# SCH__TX510__2025-04-04.net
KiCad netlist of a schematic drawn in Altium Designer
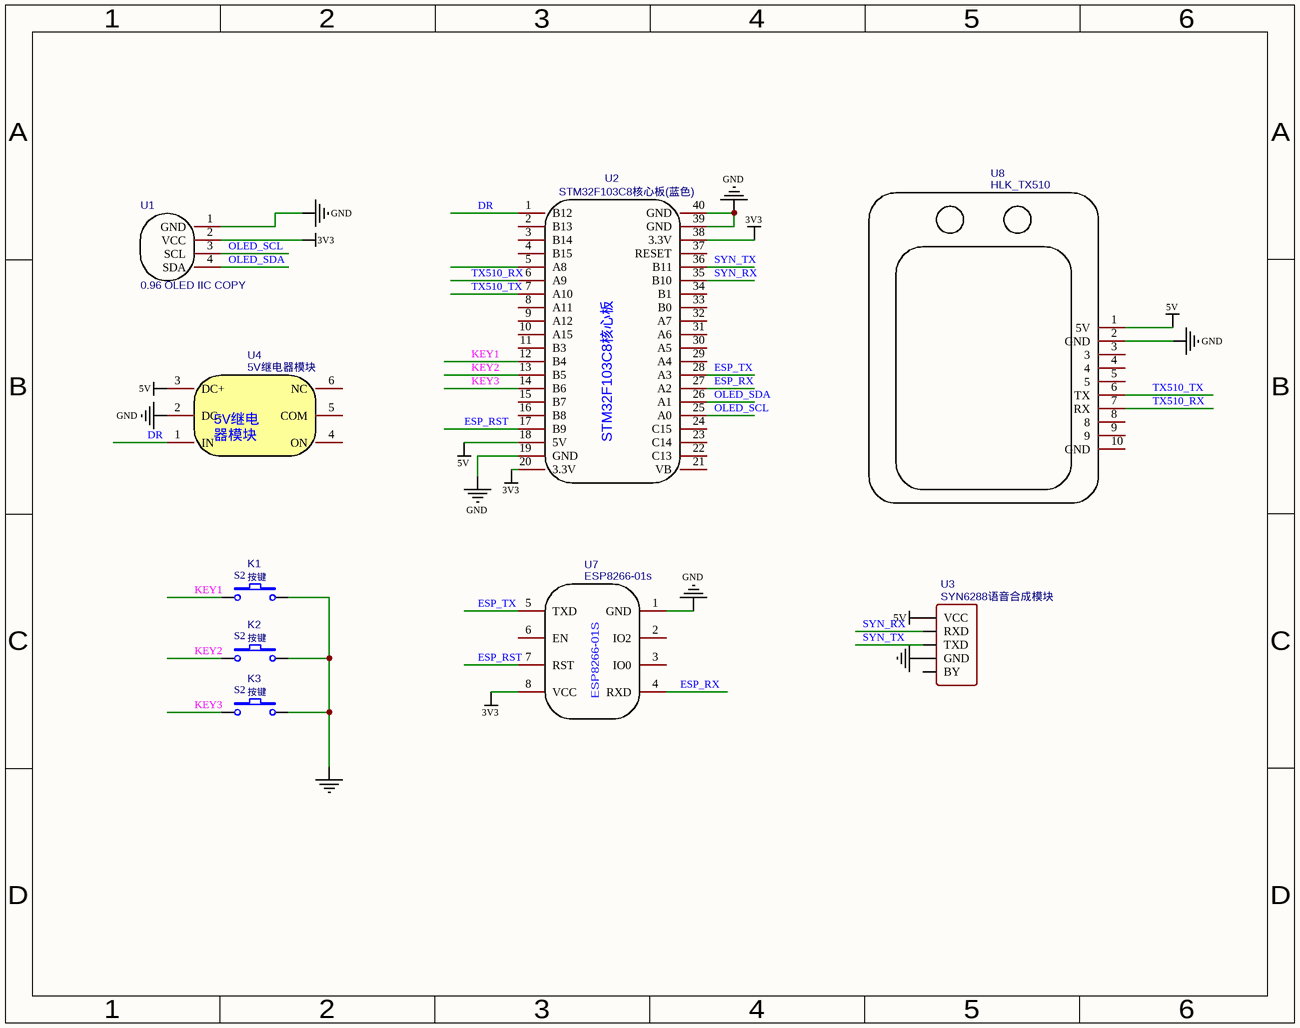
[diagram p0: SCH_人脸识别TX510和考勤_2025-04-04.schdoc]

(export (version "E")
  (design (tool "Eeschema 10.0.6"))
  (components
    (comp (ref "K1")
      (value "按键")
      (footprint "KEY-TH_4P复位按键")
      (fields (field (name "CONTRIBUTOR") "tongtongll"))
      (libsource (lib "altium-import") (part "root_1_按键_"))
    )
    (comp (ref "K2")
      (value "按键")
      (footprint "KEY-TH_4P复位按键")
      (fields (field (name "CONTRIBUTOR") "tongtongll"))
      (libsource (lib "altium-import") (part "root_1_按键_"))
    )
    (comp (ref "K3")
      (value "按键")
      (footprint "KEY-TH_4P复位按键")
      (fields (field (name "CONTRIBUTOR") "tongtongll"))
      (libsource (lib "altium-import") (part "root_1_按键_"))
    )
    (comp (ref "U1")
      (value "0.96 OLED IIC COPY")
      (footprint "OLED-TH_OLED0.96-IIC")
      (fields (field (name "CONTRIBUTOR") "0errors0warning"))
      (libsource (lib "altium-import") (part "root_0_0.96 OLED IIC COPY_"))
    )
    (comp (ref "U2")
      (value "STM32F103C8核心板(蓝色)")
      (footprint "STM32F103C8T6核心板")
      (fields (field (name "CONTRIBUTOR") "JINZH"))
      (libsource (lib "altium-import") (part "root_0_STM32F103C8核心板(蓝色)_"))
    )
    (comp (ref "U3")
      (value "SYN6288语音合成模块")
      (footprint "SYN6288语音合成模块")
      (fields (field (name "CONTRIBUTOR") "qq757683348"))
      (libsource (lib "altium-import") (part "root_0_SYN6288语音合成模块_"))
    )
    (comp (ref "U4")
      (value "5V继电器模块")
      (footprint "5V继电器模块")
      (fields (field (name "CONTRIBUTOR") "zxt_esp8266"))
      (libsource (lib "altium-import") (part "root_2_5V继电器模块_"))
    )
    (comp (ref "U7")
      (value "ESP8266-01s")
      (footprint "ESP8266-01S")
      (fields (field (name "CONTRIBUTOR") "weidu"))
      (libsource (lib "altium-import") (part "root_3_ESP8266-01s_"))
    )
    (comp (ref "U8")
      (value "HLK_TX510")
      (footprint "TX510")
      (fields (field (name "CONTRIBUTOR") "flyinglab"))
      (libsource (lib "altium-import") (part "root_0_HLK_TX510_"))
    )
  )
  (nets
    (net (code "1") (name "/DR") (class "Default")
      (node (ref "U2") (pin "1") (pinfunction "B12_1") (pintype "passive"))
      (node (ref "U4") (pin "1") (pinfunction "IN_1") (pintype "passive"))
    )
    (net (code "2") (name "/ESP_RST") (class "Default")
      (node (ref "U2") (pin "17") (pinfunction "B9_17") (pintype "passive"))
      (node (ref "U7") (pin "7") (pinfunction "RST_7") (pintype "passive"))
    )
    (net (code "3") (name "/ESP_RX") (class "Default")
      (node (ref "U2") (pin "27") (pinfunction "A2_27") (pintype "passive"))
      (node (ref "U7") (pin "4") (pinfunction "RXD_4") (pintype "passive"))
    )
    (net (code "4") (name "/ESP_TX") (class "Default")
      (node (ref "U2") (pin "28") (pinfunction "A3_28") (pintype "passive"))
      (node (ref "U7") (pin "5") (pinfunction "TXD_5") (pintype "passive"))
    )
    (net (code "5") (name "/KEY1") (class "Default")
      (node (ref "K1") (pin "1") (pinfunction "1_1") (pintype "passive"))
      (node (ref "U2") (pin "12") (pinfunction "B4_12") (pintype "passive"))
    )
    (net (code "6") (name "/KEY2") (class "Default")
      (node (ref "K2") (pin "1") (pinfunction "1_1") (pintype "passive"))
      (node (ref "U2") (pin "13") (pinfunction "B5_13") (pintype "passive"))
    )
    (net (code "7") (name "/KEY3") (class "Default")
      (node (ref "K3") (pin "1") (pinfunction "1_1") (pintype "passive"))
      (node (ref "U2") (pin "14") (pinfunction "B6_14") (pintype "passive"))
    )
    (net (code "8") (name "/OLED_SCL") (class "Default")
      (node (ref "U1") (pin "3") (pinfunction "SCL_3") (pintype "passive"))
      (node (ref "U2") (pin "25") (pinfunction "A0_25") (pintype "passive"))
    )
    (net (code "9") (name "/OLED_SDA") (class "Default")
      (node (ref "U1") (pin "4") (pinfunction "SDA_4") (pintype "passive"))
      (node (ref "U2") (pin "26") (pinfunction "A1_26") (pintype "passive"))
    )
    (net (code "10") (name "/SYN_RX") (class "Default")
      (node (ref "U2") (pin "35") (pinfunction "B10_35") (pintype "passive"))
      (node (ref "U3") (pin "2") (pinfunction "RXD_2") (pintype "passive"))
    )
    (net (code "11") (name "/SYN_TX") (class "Default")
      (node (ref "U2") (pin "36") (pinfunction "B11_36") (pintype "passive"))
      (node (ref "U3") (pin "3") (pinfunction "TXD_3") (pintype "passive"))
    )
    (net (code "12") (name "/TX510_RX") (class "Default")
      (node (ref "U2") (pin "6") (pinfunction "A9_6") (pintype "passive"))
      (node (ref "U8") (pin "7") (pinfunction "RX_7") (pintype "passive"))
    )
    (net (code "13") (name "/TX510_TX") (class "Default")
      (node (ref "U2") (pin "7") (pinfunction "A10_7") (pintype "passive"))
      (node (ref "U8") (pin "6") (pinfunction "TX_6") (pintype "passive"))
    )
    (net (code "14") (name "3V3") (class "Default")
      (node (ref "U1") (pin "2") (pinfunction "VCC_2") (pintype "passive"))
      (node (ref "U2") (pin "20") (pinfunction "3.3V_20") (pintype "passive"))
      (node (ref "U2") (pin "38") (pinfunction "3.3V_38") (pintype "passive"))
      (node (ref "U7") (pin "8") (pinfunction "VCC_8") (pintype "passive"))
    )
    (net (code "15") (name "5V") (class "Default")
      (node (ref "U2") (pin "18") (pinfunction "5V_18") (pintype "passive"))
      (node (ref "U3") (pin "1") (pinfunction "VCC_1") (pintype "passive"))
      (node (ref "U4") (pin "3") (pinfunction "DC+_3") (pintype "passive"))
      (node (ref "U8") (pin "1") (pinfunction "5V_1") (pintype "passive"))
    )
    (net (code "16") (name "GND") (class "Default")
      (node (ref "K1") (pin "3") (pinfunction "3_3") (pintype "passive"))
      (node (ref "K2") (pin "3") (pinfunction "3_3") (pintype "passive"))
      (node (ref "K3") (pin "3") (pinfunction "3_3") (pintype "passive"))
      (node (ref "U1") (pin "1") (pinfunction "GND_1") (pintype "passive"))
      (node (ref "U2") (pin "19") (pinfunction "GND_19") (pintype "passive"))
      (node (ref "U2") (pin "39") (pinfunction "GND_39") (pintype "passive"))
      (node (ref "U2") (pin "40") (pinfunction "GND_40") (pintype "passive"))
      (node (ref "U3") (pin "4") (pinfunction "GND_4") (pintype "passive"))
      (node (ref "U4") (pin "2") (pinfunction "DC-_2") (pintype "passive"))
      (node (ref "U7") (pin "1") (pinfunction "GND_1") (pintype "passive"))
      (node (ref "U8") (pin "2") (pinfunction "GND_2") (pintype "passive"))
    )
    (net (code "17") (name "unconnected-(U2-A4-Pad29)") (class "Default")
      (node (ref "U2") (pin "29") (pinfunction "A4_29") (pintype "passive"))
    )
    (net (code "18") (name "unconnected-(U2-A5-Pad30)") (class "Default")
      (node (ref "U2") (pin "30") (pinfunction "A5_30") (pintype "passive"))
    )
    (net (code "19") (name "unconnected-(U2-A6-Pad31)") (class "Default")
      (node (ref "U2") (pin "31") (pinfunction "A6_31") (pintype "passive"))
    )
    (net (code "20") (name "unconnected-(U2-A7-Pad32)") (class "Default")
      (node (ref "U2") (pin "32") (pinfunction "A7_32") (pintype "passive"))
    )
    (net (code "21") (name "unconnected-(U2-A8-Pad5)") (class "Default")
      (node (ref "U2") (pin "5") (pinfunction "A8_5") (pintype "passive"))
    )
    (net (code "22") (name "unconnected-(U2-A11-Pad8)") (class "Default")
      (node (ref "U2") (pin "8") (pinfunction "A11_8") (pintype "passive"))
    )
    (net (code "23") (name "unconnected-(U2-A12-Pad9)") (class "Default")
      (node (ref "U2") (pin "9") (pinfunction "A12_9") (pintype "passive"))
    )
    (net (code "24") (name "unconnected-(U2-A15-Pad10)") (class "Default")
      (node (ref "U2") (pin "10") (pinfunction "A15_10") (pintype "passive"))
    )
    (net (code "25") (name "unconnected-(U2-B0-Pad33)") (class "Default")
      (node (ref "U2") (pin "33") (pinfunction "B0_33") (pintype "passive"))
    )
    (net (code "26") (name "unconnected-(U2-B1-Pad34)") (class "Default")
      (node (ref "U2") (pin "34") (pinfunction "B1_34") (pintype "passive"))
    )
    (net (code "27") (name "unconnected-(U2-B3-Pad11)") (class "Default")
      (node (ref "U2") (pin "11") (pinfunction "B3_11") (pintype "passive"))
    )
    (net (code "28") (name "unconnected-(U2-B7-Pad15)") (class "Default")
      (node (ref "U2") (pin "15") (pinfunction "B7_15") (pintype "passive"))
    )
    (net (code "29") (name "unconnected-(U2-B8-Pad16)") (class "Default")
      (node (ref "U2") (pin "16") (pinfunction "B8_16") (pintype "passive"))
    )
    (net (code "30") (name "unconnected-(U2-B13-Pad2)") (class "Default")
      (node (ref "U2") (pin "2") (pinfunction "B13_2") (pintype "passive"))
    )
    (net (code "31") (name "unconnected-(U2-B14-Pad3)") (class "Default")
      (node (ref "U2") (pin "3") (pinfunction "B14_3") (pintype "passive"))
    )
    (net (code "32") (name "unconnected-(U2-B15-Pad4)") (class "Default")
      (node (ref "U2") (pin "4") (pinfunction "B15_4") (pintype "passive"))
    )
    (net (code "33") (name "unconnected-(U2-C13-Pad22)") (class "Default")
      (node (ref "U2") (pin "22") (pinfunction "C13_22") (pintype "passive"))
    )
    (net (code "34") (name "unconnected-(U2-C14-Pad23)") (class "Default")
      (node (ref "U2") (pin "23") (pinfunction "C14_23") (pintype "passive"))
    )
    (net (code "35") (name "unconnected-(U2-C15-Pad24)") (class "Default")
      (node (ref "U2") (pin "24") (pinfunction "C15_24") (pintype "passive"))
    )
    (net (code "36") (name "unconnected-(U2-RESET-Pad37)") (class "Default")
      (node (ref "U2") (pin "37") (pinfunction "RESET_37") (pintype "passive"))
    )
    (net (code "37") (name "unconnected-(U2-VB-Pad21)") (class "Default")
      (node (ref "U2") (pin "21") (pinfunction "VB_21") (pintype "passive"))
    )
    (net (code "38") (name "unconnected-(U3-BY-Pad5)") (class "Default")
      (node (ref "U3") (pin "5") (pinfunction "BY_5") (pintype "passive"))
    )
    (net (code "39") (name "unconnected-(U4-COM-Pad5)") (class "Default")
      (node (ref "U4") (pin "5") (pinfunction "COM_5") (pintype "passive"))
    )
    (net (code "40") (name "unconnected-(U4-NC-Pad6)") (class "Default")
      (node (ref "U4") (pin "6") (pinfunction "NC_6") (pintype "passive"))
    )
    (net (code "41") (name "unconnected-(U4-ON-Pad4)") (class "Default")
      (node (ref "U4") (pin "4") (pinfunction "ON_4") (pintype "passive"))
    )
    (net (code "42") (name "unconnected-(U7-EN-Pad6)") (class "Default")
      (node (ref "U7") (pin "6") (pinfunction "EN_6") (pintype "passive"))
    )
    (net (code "43") (name "unconnected-(U7-IO0-Pad3)") (class "Default")
      (node (ref "U7") (pin "3") (pinfunction "IO0_3") (pintype "passive"))
    )
    (net (code "44") (name "unconnected-(U7-IO2-Pad2)") (class "Default")
      (node (ref "U7") (pin "2") (pinfunction "IO2_2") (pintype "passive"))
    )
    (net (code "45") (name "unconnected-(U8-GND-Pad10)") (class "Default")
      (node (ref "U8") (pin "10") (pinfunction "GND_10") (pintype "passive"))
    )
    (net (code "46") (name "unconnected-(U8-Pad3)") (class "Default")
      (node (ref "U8") (pin "3") (pinfunction "3_3") (pintype "passive"))
    )
    (net (code "47") (name "unconnected-(U8-Pad4)") (class "Default")
      (node (ref "U8") (pin "4") (pinfunction "4_4") (pintype "passive"))
    )
    (net (code "48") (name "unconnected-(U8-Pad5)") (class "Default")
      (node (ref "U8") (pin "5") (pinfunction "5_5") (pintype "passive"))
    )
    (net (code "49") (name "unconnected-(U8-Pad8)") (class "Default")
      (node (ref "U8") (pin "8") (pinfunction "8_8") (pintype "passive"))
    )
    (net (code "50") (name "unconnected-(U8-Pad9)") (class "Default")
      (node (ref "U8") (pin "9") (pinfunction "9_9") (pintype "passive"))
    )
  )
)
